# button_breakout.net
KiCad netlist of a schematic drawn in EAGLE
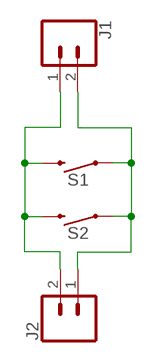
[diagram p0: schematic, sheet 1]

(export (version "E")
  (design (tool "Eeschema 10.0.6"))
  (components
    (comp (ref "J1")
      (value "CONN_02LOCK")
      (footprint "eagle-import:1X02_LOCK")
      (libsource (lib "eagle-import") (part "CONN_02LOCK"))
    )
    (comp (ref "J2")
      (value "CONN_023.5MM_LOCK")
      (footprint "eagle-import:SCREWTERMINAL-3.5MM-2_LOCK")
      (libsource (lib "eagle-import") (part "CONN_023.5MM_LOCK"))
    )
    (comp (ref "S1")
      (value "MOMENTARY-SWITCH-SPST-PTH-12MM")
      (footprint "eagle-import:TACTILE_SWITCH_PTH_12MM")
      (libsource (lib "eagle-import") (part "MOMENTARY-SWITCH-SPST-PTH-12MM"))
    )
    (comp (ref "S2")
      (value "MOMENTARY-SWITCH-SPST-PTH-6.0MM")
      (footprint "eagle-import:TACTILE_SWITCH_PTH_6.0MM")
      (libsource (lib "eagle-import") (part "MOMENTARY-SWITCH-SPST-PTH-6.0MM"))
    )
  )
  (nets
    (net (code "1") (name "Net-(J1-Pad2)") (class "Default")
      (node (ref "J1") (pin "2") (pinfunction "2_2") (pintype "passive"))
      (node (ref "J2") (pin "1") (pinfunction "1_1") (pintype "passive"))
      (node (ref "S1") (pin "1") (pinfunction "1_1") (pintype "passive"))
      (node (ref "S2") (pin "1") (pinfunction "1_1") (pintype "passive"))
    )
    (net (code "2") (name "Net-(S1-2)") (class "Default")
      (node (ref "J1") (pin "1") (pinfunction "1_1") (pintype "passive"))
      (node (ref "J2") (pin "2") (pinfunction "2_2") (pintype "passive"))
      (node (ref "S1") (pin "3") (pinfunction "2_3") (pintype "passive"))
      (node (ref "S2") (pin "3") (pinfunction "2_3") (pintype "passive"))
    )
  )
)
